# Lan.net
KiCad netlist of a schematic drawn in Altium Designer
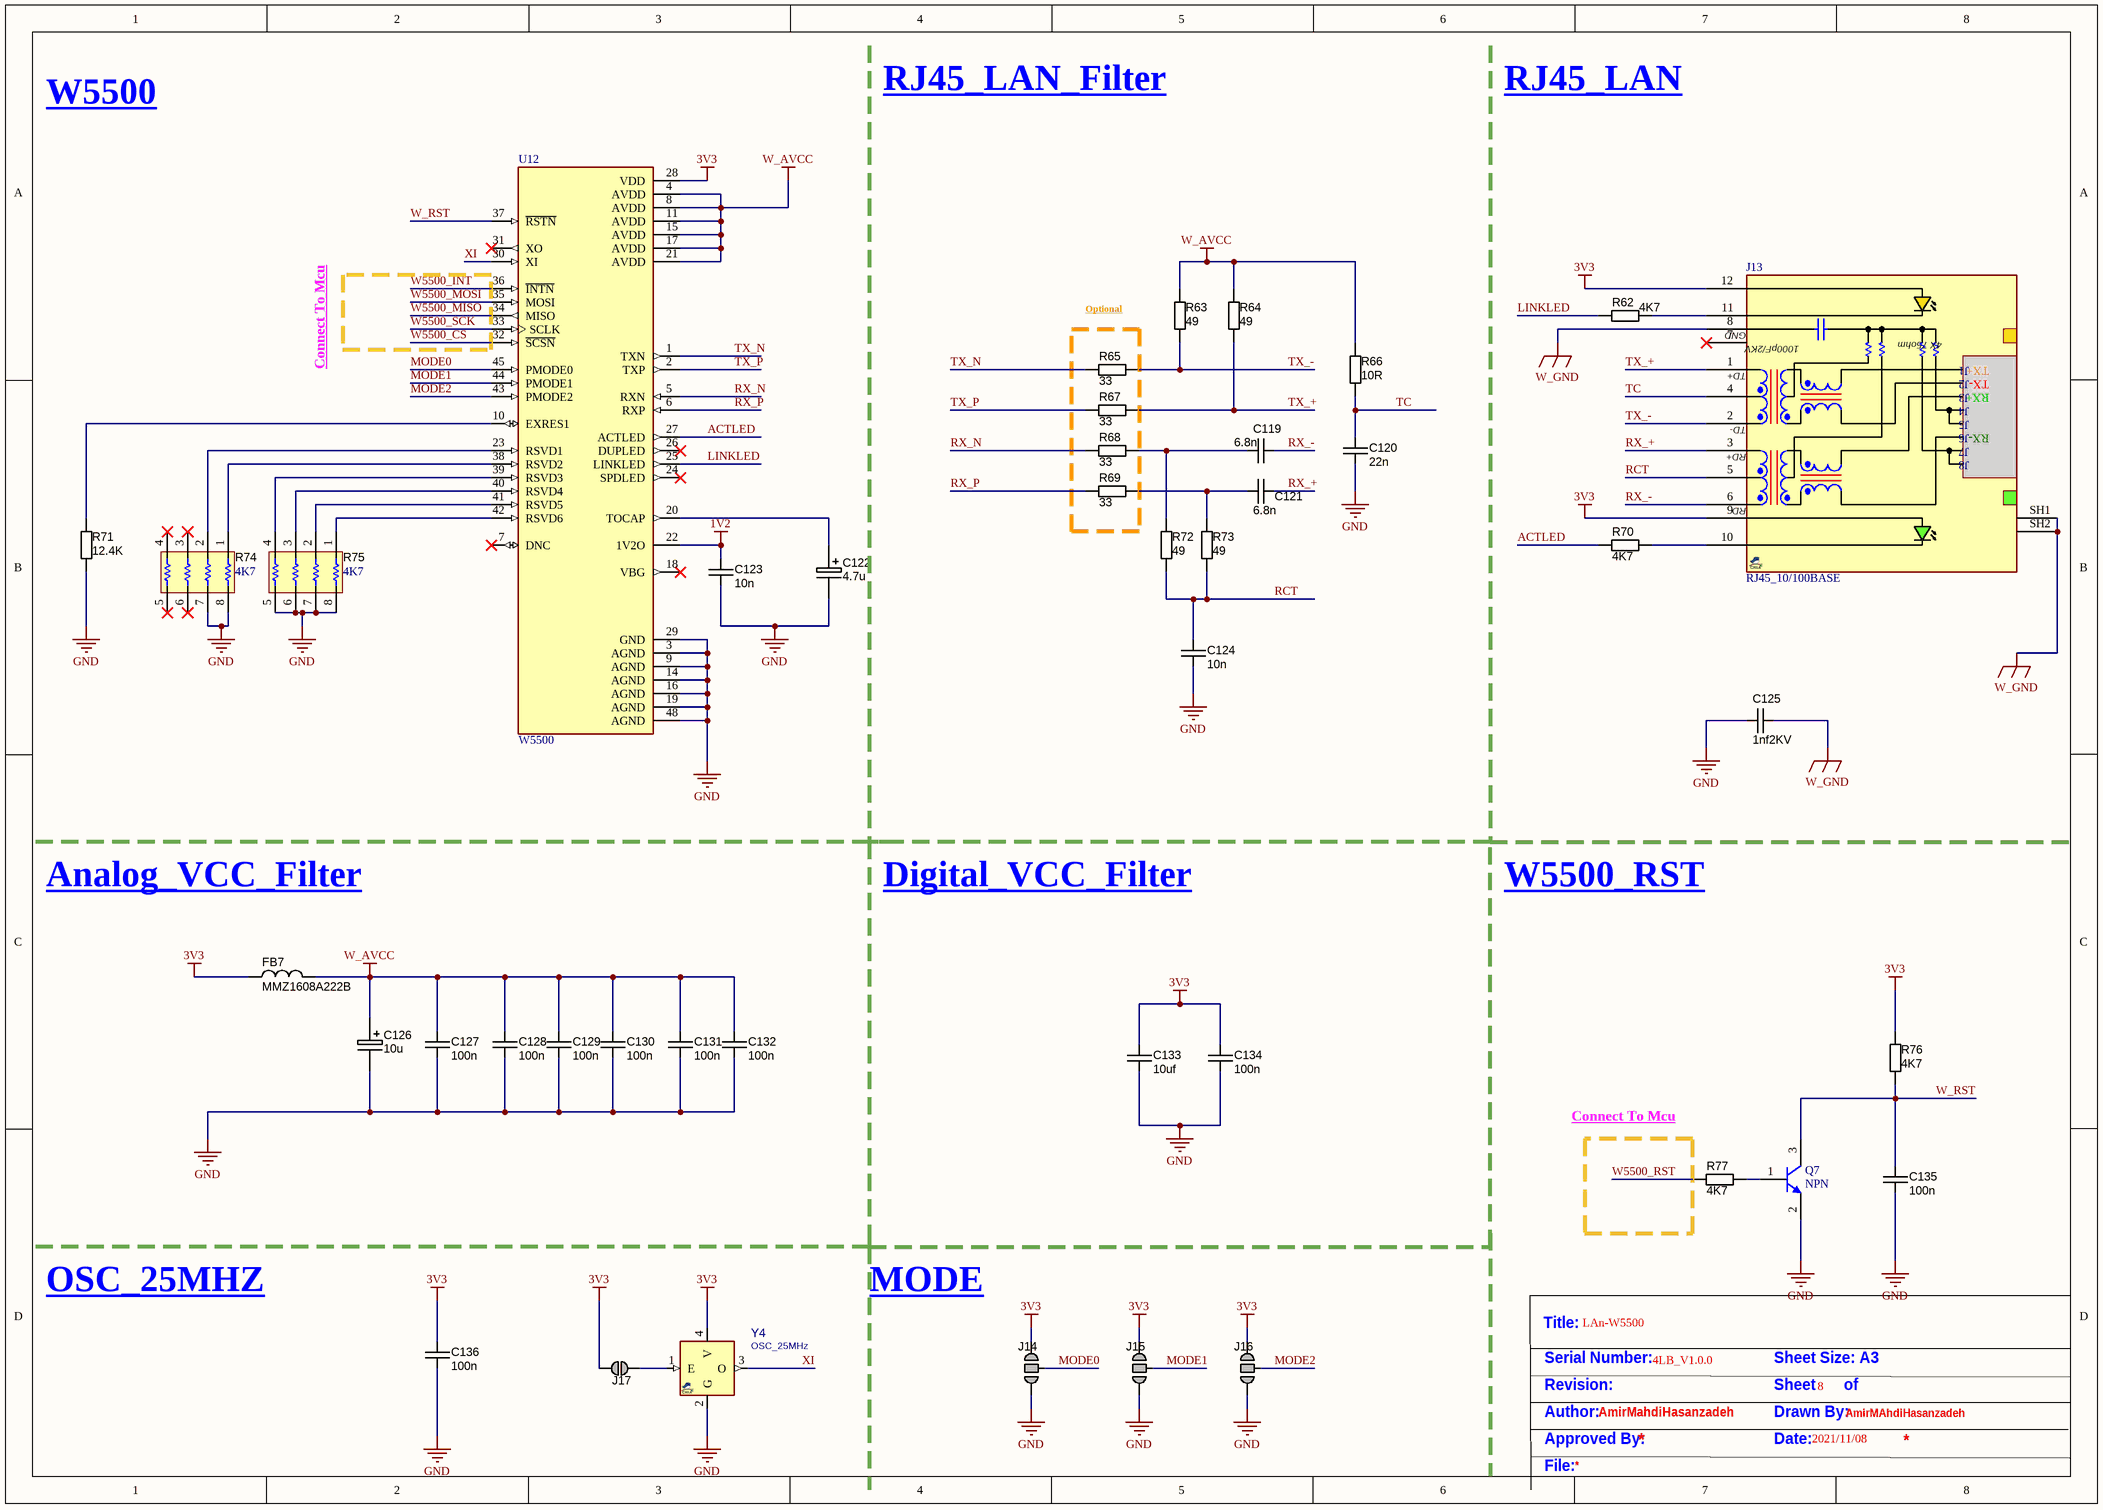
[diagram p0: Lan.SchDoc]

(export (version "E")
  (design (tool "Eeschema 10.0.6"))
  (components
    (comp (ref "C119")
      (value "6.8n")
      (footprint "CAPC1608X90N")
      (description "Capacitor SMD Cer 6.8 10% 50V X7R 0603")
      (fields (field (name "TOLERANCE") "±10%") (field (name "Comment") "approved sub OK"))
      (libsource (lib "PBL - Capacitors") (part "CAPC_100n_0603_X7R_50V_10%"))
    )
    (comp (ref "C120")
      (value "22n")
      (footprint "CAPC1608X90N")
      (description "Capacitor SMD Cer 100nF 10% 50V X7R 0603")
      (fields (field (name "TOLERANCE") "±10%") (field (name "Comment") "approved sub OK"))
      (libsource (lib "PBL - Capacitors") (part "CAPC_100n_0603_X7R_50V_10%"))
    )
    (comp (ref "C121")
      (value "6.8n")
      (footprint "CAPC1608X90N")
      (description "Capacitor SMD Cer 6.8nf 10% 50V X7R 0603")
      (fields (field (name "TOLERANCE") "±10%") (field (name "Comment") "approved sub OK"))
      (libsource (lib "PBL - Capacitors") (part "CAPC_100n_0603_X7R_50V_10%"))
    )
    (comp (ref "C122")
      (value "4.7u")
      (footprint "C_TN_3216")
      (description "Capacitor SMD Tantalum 4.7uF 10% 16V 3216-18")
      (fields (field (name "TOLERANCE") "±10%"))
      (libsource (lib "PBL - Capacitors") (part "CAPT_4u7_3216_16V"))
    )
    (comp (ref "C123")
      (value "10n")
      (footprint "CAPC1608X90N")
      (description "Capacitor SMD Cer 10nF 10% 50V X7R 0603")
      (fields (field (name "TOLERANCE") "±10%") (field (name "Comment") "approved sub OK"))
      (libsource (lib "PBL - Capacitors") (part "CAPC_100n_0603_X7R_50V_10%"))
    )
    (comp (ref "C124")
      (value "10n")
      (footprint "CAPC1608X90N")
      (description "Capacitor SMD Cer 100nF 10% 50V X7R 0603")
      (fields (field (name "TOLERANCE") "±10%") (field (name "Comment") "approved sub OK"))
      (libsource (lib "PBL - Capacitors") (part "CAPC_100n_0603_X7R_50V_10%"))
    )
    (comp (ref "C125")
      (value "1nf2KV")
      (footprint "C1206")
      (description "Capacitor SMD Cer 1nF 10% 2kv X7R 0603")
      (fields (field (name "TOLERANCE") "±10%") (field (name "Comment") "approved sub OK"))
      (libsource (lib "PBL - Capacitors") (part "CAPC_100n_0603_X7R_50V_10%"))
    )
    (comp (ref "C126")
      (value "10u")
      (footprint "C_TN_3216")
      (description "Capacitor SMD Tantalum 10uF 10% 16V 3216-18")
      (fields (field (name "TOLERANCE") "±10%"))
      (libsource (lib "PBL - Capacitors") (part "CAPT_4u7_3216_16V"))
    )
    (comp (ref "C127")
      (value "100n")
      (footprint "CAPC1608X90N")
      (description "Capacitor SMD Cer 100nF 10% 50V X7R 0603")
      (fields (field (name "TOLERANCE") "±10%") (field (name "Comment") "approved sub OK"))
      (libsource (lib "PBL - Capacitors") (part "CAPC_100n_0603_X7R_50V_10%"))
    )
    (comp (ref "C128")
      (value "100n")
      (footprint "CAPC1608X90N")
      (description "Capacitor SMD Cer 100nF 10% 50V X7R 0603")
      (fields (field (name "TOLERANCE") "±10%") (field (name "Comment") "approved sub OK"))
      (libsource (lib "PBL - Capacitors") (part "CAPC_100n_0603_X7R_50V_10%"))
    )
    (comp (ref "C129")
      (value "100n")
      (footprint "CAPC1608X90N")
      (description "Capacitor SMD Cer 100nF 10% 50V X7R 0603")
      (fields (field (name "TOLERANCE") "±10%") (field (name "Comment") "approved sub OK"))
      (libsource (lib "PBL - Capacitors") (part "CAPC_100n_0603_X7R_50V_10%"))
    )
    (comp (ref "C130")
      (value "100n")
      (footprint "CAPC1608X90N")
      (description "Capacitor SMD Cer 100nF 10% 50V X7R 0603")
      (fields (field (name "TOLERANCE") "±10%") (field (name "Comment") "approved sub OK"))
      (libsource (lib "PBL - Capacitors") (part "CAPC_100n_0603_X7R_50V_10%"))
    )
    (comp (ref "C131")
      (value "100n")
      (footprint "CAPC1608X90N")
      (description "Capacitor SMD Cer 100nF 10% 50V X7R 0603")
      (fields (field (name "TOLERANCE") "±10%") (field (name "Comment") "approved sub OK"))
      (libsource (lib "PBL - Capacitors") (part "CAPC_100n_0603_X7R_50V_10%"))
    )
    (comp (ref "C132")
      (value "100n")
      (footprint "CAPC1608X90N")
      (description "Capacitor SMD Cer 100nF 10% 50V X7R 0603")
      (fields (field (name "TOLERANCE") "±10%") (field (name "Comment") "approved sub OK"))
      (libsource (lib "PBL - Capacitors") (part "CAPC_100n_0603_X7R_50V_10%"))
    )
    (comp (ref "C133")
      (value "10uf")
      (footprint "CAPC1608X90N")
      (description "Capacitor SMD Cer 100nF 10% 50V X7R 0603")
      (fields (field (name "TOLERANCE") "±10%") (field (name "Comment") "approved sub OK"))
      (libsource (lib "PBL - Capacitors") (part "CAPC_100n_0603_X7R_50V_10%"))
    )
    (comp (ref "C134")
      (value "100n")
      (footprint "CAPC1608X90N")
      (description "Capacitor SMD Cer 100nF 10% 50V X7R 0603")
      (fields (field (name "TOLERANCE") "±10%") (field (name "Comment") "approved sub OK"))
      (libsource (lib "PBL - Capacitors") (part "CAPC_100n_0603_X7R_50V_10%"))
    )
    (comp (ref "C135")
      (value "100n")
      (footprint "CAPC1608X90N")
      (description "Capacitor SMD Cer 100nF 10% 50V X7R 0603")
      (fields (field (name "TOLERANCE") "±10%") (field (name "Comment") "approved sub OK"))
      (libsource (lib "PBL - Capacitors") (part "CAPC_100n_0603_X7R_50V_10%"))
    )
    (comp (ref "C136")
      (value "100n")
      (footprint "CAPC1608X90N")
      (description "Capacitor SMD Cer 100nF 10% 50V X7R 0603")
      (fields (field (name "TOLERANCE") "±10%") (field (name "Comment") "approved sub OK"))
      (libsource (lib "PBL - Capacitors") (part "CAPC_100n_0603_X7R_50V_10%"))
    )
    (comp (ref "FB7")
      (value "2K2 @ 100 MHz")
      (footprint "FBC1608X95N")
      (description "Ferrite bead 2.2K Ohm at 100 MHz 200mA 0603 SMD")
      (fields (field (name "MANUFACTURER PART NUMBER 1") "MMZ1608A222B"))
      (libsource (lib "PBL - Inductors") (part "FERRITE_2K2-100MHz_0603"))
    )
    (comp (ref "J13")
      (value "RJ45_10/100BASE")
      (footprint "RJ45_8M_HR911105A")
      (description "RJ45, 10/100BASE, G/Y LED")
      (fields (field (name "MANF") "Hanrun") (field (name "MANF_P#") "HR911105A"))
      (libsource (lib "conn_rj_ModularJack") (part "RJ45_HR911105A"))
    )
    (comp (ref "J14")
      (value "Jumper")
      (footprint "Jump_3Way")
      (description "SMD jumper")
      (libsource (lib "PBL - Pads and Jumpers") (part "JUMP_3WAY"))
    )
    (comp (ref "J15")
      (value "Jumper")
      (footprint "Jump_3Way")
      (description "SMD jumper")
      (libsource (lib "PBL - Pads and Jumpers") (part "JUMP_3WAY"))
    )
    (comp (ref "J16")
      (value "Jumper")
      (footprint "Jump_3Way")
      (description "SMD jumper")
      (libsource (lib "PBL - Pads and Jumpers") (part "JUMP_3WAY"))
    )
    (comp (ref "J17")
      (value "Jumper")
      (footprint "JUMP1")
      (description "SMD jumper")
      (libsource (lib "PBL - Pads and Jumpers") (part "JUMP1"))
    )
    (comp (ref "Q7")
      (value "NPN")
      (footprint "SOT23-3")
      (description "NPN Bipolar Transistor")
      (fields (field (name "PUBLISHER") "Altium Limited"))
      (libsource (lib "Miscellaneous Devices") (part "NPN"))
    )
    (comp (ref "R62")
      (value "4K7")
      (footprint "RESC1608X55N")
      (description "Resistor SMD chip 4.7k Ohm 0.1W 5% 0603")
      (fields (field (name "TOLERANCE") "±5%") (field (name "Comment") "Thick Film"))
      (libsource (lib "") (part "RES_4K7_0603_5%_1"))
    )
    (comp (ref "R63")
      (value "49")
      (footprint "RESC1608X55N")
      (description "Resistor SMD chip 49 Ohm 0.1W 5% 0603")
      (fields (field (name "TOLERANCE") "±5%") (field (name "Comment") "Thick Film"))
      (libsource (lib "PBL - Resistors") (part "RES_4K7_0603_5%"))
    )
    (comp (ref "R64")
      (value "49")
      (footprint "RESC1608X55N")
      (description "Resistor SMD chip 49 Ohm 0.1W 5% 0603")
      (fields (field (name "TOLERANCE") "±5%") (field (name "Comment") "Thick Film"))
      (libsource (lib "PBL - Resistors") (part "RES_4K7_0603_5%"))
    )
    (comp (ref "R65")
      (value "33")
      (footprint "RESC1608X55N")
      (description "Resistor SMD chip 33 Ohm 0.1W 5% 0603")
      (fields (field (name "TOLERANCE") "±5%") (field (name "Comment") "Thick Film"))
      (libsource (lib "") (part "RES_4K7_0603_5%_1"))
    )
    (comp (ref "R66")
      (value "10R")
      (footprint "RESC1608X55N")
      (description "Resistor SMD chip 10 Ohm 0.1W 5% 0603")
      (fields (field (name "TOLERANCE") "±5%") (field (name "Comment") "Thick Film"))
      (libsource (lib "PBL - Resistors") (part "RES_4K7_0603_5%"))
    )
    (comp (ref "R67")
      (value "33")
      (footprint "RESC1608X55N")
      (description "Resistor SMD chip 33 Ohm 0.1W 5% 0603")
      (fields (field (name "TOLERANCE") "±5%") (field (name "Comment") "Thick Film"))
      (libsource (lib "") (part "RES_4K7_0603_5%_1"))
    )
    (comp (ref "R68")
      (value "33")
      (footprint "RESC1608X55N")
      (description "Resistor SMD chip 33 Ohm 0.1W 5% 0603")
      (fields (field (name "TOLERANCE") "±5%") (field (name "Comment") "Thick Film"))
      (libsource (lib "") (part "RES_4K7_0603_5%_1"))
    )
    (comp (ref "R69")
      (value "33")
      (footprint "RESC1608X55N")
      (description "Resistor SMD chip 33 Ohm 0.1W 5% 0603")
      (fields (field (name "TOLERANCE") "±5%") (field (name "Comment") "Thick Film"))
      (libsource (lib "") (part "RES_4K7_0603_5%_1"))
    )
    (comp (ref "R70")
      (value "4K7")
      (footprint "RESC1608X55N")
      (description "Resistor SMD chip 4.7k Ohm 0.1W 5% 0603")
      (fields (field (name "TOLERANCE") "±5%") (field (name "Comment") "Thick Film"))
      (libsource (lib "") (part "RES_4K7_0603_5%_1"))
    )
    (comp (ref "R71")
      (value "12.4K")
      (footprint "RESC1608X55N")
      (description "Resistor SMD chip 12.4K Ohm 0.1W 1% 0603")
      (fields (field (name "TOLERANCE") "±5%") (field (name "Comment") "Thick Film"))
      (libsource (lib "") (part "RES_4K7_0603_5%_1"))
    )
    (comp (ref "R72")
      (value "49")
      (footprint "RESC1608X55N")
      (description "Resistor SMD chip 49 Ohm 0.1W 5% 0603")
      (fields (field (name "TOLERANCE") "±5%") (field (name "Comment") "Thick Film"))
      (libsource (lib "PBL - Resistors") (part "RES_4K7_0603_5%"))
    )
    (comp (ref "R73")
      (value "49")
      (footprint "RESC1608X55N")
      (description "Resistor SMD chip 49 Ohm 0.1W 5% 0603")
      (fields (field (name "TOLERANCE") "±5%") (field (name "Comment") "Thick Film"))
      (libsource (lib "PBL - Resistors") (part "RES_4K7_0603_5%"))
    )
    (comp (ref "R74")
      (value "4K7")
      (footprint "RP0603X4")
      (description "Resistor Array SMD")
      (libsource (lib "Resistor") (part "Resistor Array SMD"))
    )
    (comp (ref "R75")
      (value "4K7")
      (footprint "RP0603X4")
      (description "Resistor Array SMD")
      (libsource (lib "Resistor") (part "Resistor Array SMD"))
    )
    (comp (ref "R76")
      (value "4K7")
      (footprint "RESC1608X55N")
      (description "Resistor SMD chip 4.7k Ohm 0.1W 5% 0603")
      (fields (field (name "TOLERANCE") "±5%") (field (name "Comment") "Thick Film"))
      (libsource (lib "") (part "RES_4K7_0603_5%_2"))
    )
    (comp (ref "R77")
      (value "4K7")
      (footprint "RESC1608X55N")
      (description "Resistor SMD chip 4.7k Ohm 0.1W 5% 0603")
      (fields (field (name "TOLERANCE") "±5%") (field (name "Comment") "Thick Film"))
      (libsource (lib "PBL - Resistors") (part "RES_4K7_0603_5%"))
    )
    (comp (ref "U12")
      (value "W5500")
      (footprint "LQFP-48_N")
      (description "Socket Contact Silver 17-20 AWG Crimp Power")
      (fields (field (name "MF") "WIZnet"))
      (libsource (lib "W5500") (part "W5500"))
    )
    (comp (ref "Y4")
      (value "OSC_25MHz")
      (footprint "XTL_4_2520")
      (description "CLOCK OSCILLATOR, 25MHz, 10PPM, 3.2X2.5mm")
      (fields (field (name "MANF") "ECS") (field (name "MANF_P#") "ECS-3225S18-250-FN-TR"))
      (libsource (lib "crystal_osc") (part "OSC_4_25MHz_3225E"))
    )
  )
  (nets
    (net (code "1") (name "/ACTLED") (class "Default")
      (node (ref "R70") (pin "1") (pinfunction "1_1") (pintype "passive"))
      (node (ref "U12") (pin "27") (pinfunction "ACTLED_27") (pintype "output"))
    )
    (net (code "2") (name "/LINKLED") (class "Default")
      (node (ref "R62") (pin "1") (pinfunction "1_1") (pintype "passive"))
      (node (ref "U12") (pin "25") (pinfunction "LINKLED_25") (pintype "output"))
    )
    (net (code "3") (name "/MODE0") (class "Default")
      (node (ref "J14") (pin "2") (pinfunction "2_2") (pintype "passive"))
      (node (ref "U12") (pin "45") (pinfunction "PMODE0_45") (pintype "input"))
    )
    (net (code "4") (name "/MODE1") (class "Default")
      (node (ref "J15") (pin "2") (pinfunction "2_2") (pintype "passive"))
      (node (ref "U12") (pin "44") (pinfunction "PMODE1_44") (pintype "input"))
    )
    (net (code "5") (name "/MODE2") (class "Default")
      (node (ref "J16") (pin "2") (pinfunction "2_2") (pintype "passive"))
      (node (ref "U12") (pin "43") (pinfunction "PMODE2_43") (pintype "input"))
    )
    (net (code "6") (name "/RCT") (class "Default")
      (node (ref "C124") (pin "1") (pintype "passive"))
      (node (ref "J13") (pin "5") (pinfunction "RCT_5") (pintype "passive"))
      (node (ref "R72") (pin "1") (pinfunction "1_1") (pintype "passive"))
      (node (ref "R73") (pin "1") (pinfunction "1_1") (pintype "passive"))
    )
    (net (code "7") (name "/RX_+") (class "Default")
      (node (ref "C121") (pin "2") (pintype "passive"))
      (node (ref "J13") (pin "3") (pinfunction "RD+_3") (pintype "passive"))
    )
    (net (code "8") (name "/RX_-") (class "Default")
      (node (ref "C119") (pin "2") (pintype "passive"))
      (node (ref "J13") (pin "6") (pinfunction "RD-_6") (pintype "passive"))
    )
    (net (code "9") (name "/RX_N") (class "Default")
      (node (ref "R68") (pin "1") (pinfunction "1_1") (pintype "passive"))
      (node (ref "U12") (pin "5") (pinfunction "RXN_5") (pintype "input"))
    )
    (net (code "10") (name "/RX_P") (class "Default")
      (node (ref "R69") (pin "1") (pinfunction "1_1") (pintype "passive"))
      (node (ref "U12") (pin "6") (pinfunction "RXP_6") (pintype "input"))
    )
    (net (code "11") (name "/TC") (class "Default")
      (node (ref "C120") (pin "1") (pintype "passive"))
      (node (ref "J13") (pin "4") (pinfunction "TCT_4") (pintype "passive"))
      (node (ref "R66") (pin "1") (pinfunction "1_1") (pintype "passive"))
    )
    (net (code "12") (name "/TX_+") (class "Default")
      (node (ref "J13") (pin "1") (pinfunction "TD+_1") (pintype "passive"))
      (node (ref "R64") (pin "1") (pinfunction "1_1") (pintype "passive"))
      (node (ref "R67") (pin "2") (pinfunction "2_2") (pintype "passive"))
    )
    (net (code "13") (name "/TX_-") (class "Default")
      (node (ref "J13") (pin "2") (pinfunction "TD-_2") (pintype "passive"))
      (node (ref "R63") (pin "1") (pinfunction "1_1") (pintype "passive"))
      (node (ref "R65") (pin "2") (pinfunction "2_2") (pintype "passive"))
    )
    (net (code "14") (name "/TX_N") (class "Default")
      (node (ref "R65") (pin "1") (pinfunction "1_1") (pintype "passive"))
      (node (ref "U12") (pin "1") (pinfunction "TXN_1") (pintype "output"))
    )
    (net (code "15") (name "/TX_P") (class "Default")
      (node (ref "R67") (pin "1") (pinfunction "1_1") (pintype "passive"))
      (node (ref "U12") (pin "2") (pinfunction "TXP_2") (pintype "output"))
    )
    (net (code "16") (name "/W5500_CS") (class "Default")
      (node (ref "U12") (pin "32") (pinfunction "~{SCSN}_32") (pintype "input"))
    )
    (net (code "17") (name "/W5500_INT") (class "Default")
      (node (ref "U12") (pin "36") (pinfunction "~{INTN}_36") (pintype "input"))
    )
    (net (code "18") (name "/W5500_MISO") (class "Default")
      (node (ref "U12") (pin "34") (pinfunction "MISO_34") (pintype "output"))
    )
    (net (code "19") (name "/W5500_MOSI") (class "Default")
      (node (ref "U12") (pin "35") (pinfunction "MOSI_35") (pintype "input"))
    )
    (net (code "20") (name "/W5500_RST") (class "Default")
      (node (ref "R77") (pin "1") (pinfunction "1_1") (pintype "passive"))
    )
    (net (code "21") (name "/W5500_SCK") (class "Default")
      (node (ref "U12") (pin "33") (pinfunction "SCLK_33") (pintype "input"))
    )
    (net (code "22") (name "/W_RST") (class "Default")
      (node (ref "C135") (pin "1") (pintype "passive"))
      (node (ref "Q7") (pin "3") (pinfunction "C_3") (pintype "passive"))
      (node (ref "R76") (pin "2") (pinfunction "2_2") (pintype "passive"))
      (node (ref "U12") (pin "37") (pinfunction "~{RSTN}_37") (pintype "input"))
    )
    (net (code "23") (name "/XI") (class "Default")
      (node (ref "U12") (pin "30") (pinfunction "XI_30") (pintype "input"))
      (node (ref "Y4") (pin "3") (pinfunction "O_3") (pintype "output"))
    )
    (net (code "24") (name "1V2") (class "Default")
      (node (ref "C123") (pin "1") (pintype "passive"))
      (node (ref "U12") (pin "22") (pinfunction "1V2O_22") (pintype "power_in"))
    )
    (net (code "25") (name "3V3") (class "Default")
      (node (ref "C133") (pin "1") (pintype "passive"))
      (node (ref "C134") (pin "1") (pintype "passive"))
      (node (ref "C136") (pin "1") (pintype "passive"))
      (node (ref "FB7") (pin "1") (pinfunction "1_1") (pintype "passive"))
      (node (ref "J13") (pin "12") (pinfunction "YLED+_12") (pintype "passive"))
      (node (ref "J13") (pin "9") (pinfunction "GLED+_9") (pintype "passive"))
      (node (ref "J14") (pin "3") (pinfunction "3_3") (pintype "passive"))
      (node (ref "J15") (pin "3") (pinfunction "3_3") (pintype "passive"))
      (node (ref "J16") (pin "3") (pinfunction "3_3") (pintype "passive"))
      (node (ref "J17") (pin "2") (pintype "passive"))
      (node (ref "R76") (pin "1") (pinfunction "1_1") (pintype "passive"))
      (node (ref "U12") (pin "28") (pinfunction "VDD_28") (pintype "power_in"))
      (node (ref "Y4") (pin "4") (pinfunction "V_4") (pintype "power_in"))
    )
    (net (code "26") (name "GND") (class "Default")
      (node (ref "C120") (pin "2") (pintype "passive"))
      (node (ref "C122") (pin "2") (pintype "passive"))
      (node (ref "C123") (pin "2") (pintype "passive"))
      (node (ref "C124") (pin "2") (pintype "passive"))
      (node (ref "C125") (pin "1") (pintype "passive"))
      (node (ref "C126") (pin "2") (pintype "passive"))
      (node (ref "C127") (pin "2") (pintype "passive"))
      (node (ref "C128") (pin "2") (pintype "passive"))
      (node (ref "C129") (pin "2") (pintype "passive"))
      (node (ref "C130") (pin "2") (pintype "passive"))
      (node (ref "C131") (pin "2") (pintype "passive"))
      (node (ref "C132") (pin "2") (pintype "passive"))
      (node (ref "C133") (pin "2") (pintype "passive"))
      (node (ref "C134") (pin "2") (pintype "passive"))
      (node (ref "C135") (pin "2") (pintype "passive"))
      (node (ref "C136") (pin "2") (pintype "passive"))
      (node (ref "J14") (pin "1") (pinfunction "1_1") (pintype "passive"))
      (node (ref "J15") (pin "1") (pinfunction "1_1") (pintype "passive"))
      (node (ref "J16") (pin "1") (pinfunction "1_1") (pintype "passive"))
      (node (ref "Q7") (pin "2") (pinfunction "E_2") (pintype "passive"))
      (node (ref "R71") (pin "1") (pinfunction "1_1") (pintype "passive"))
      (node (ref "R74") (pin "7") (pinfunction "7_7") (pintype "passive"))
      (node (ref "R74") (pin "8") (pinfunction "8_8") (pintype "passive"))
      (node (ref "R75") (pin "5") (pinfunction "5_5") (pintype "passive"))
      (node (ref "R75") (pin "6") (pinfunction "6_6") (pintype "passive"))
      (node (ref "R75") (pin "7") (pinfunction "7_7") (pintype "passive"))
      (node (ref "R75") (pin "8") (pinfunction "8_8") (pintype "passive"))
      (node (ref "U12") (pin "14") (pinfunction "AGND_14") (pintype "power_in"))
      (node (ref "U12") (pin "16") (pinfunction "AGND_16") (pintype "power_in"))
      (node (ref "U12") (pin "19") (pinfunction "AGND_19") (pintype "power_in"))
      (node (ref "U12") (pin "29") (pinfunction "GND_29") (pintype "passive"))
      (node (ref "U12") (pin "3") (pinfunction "AGND_3") (pintype "power_in"))
      (node (ref "U12") (pin "48") (pinfunction "AGND_48") (pintype "power_in"))
      (node (ref "U12") (pin "9") (pinfunction "AGND_9") (pintype "power_in"))
      (node (ref "Y4") (pin "2") (pinfunction "G_2") (pintype "power_in"))
    )
    (net (code "27") (name "Net-(C119-Pad1)") (class "Default")
      (node (ref "C119") (pin "1") (pintype "passive"))
      (node (ref "R68") (pin "2") (pinfunction "2_2") (pintype "passive"))
      (node (ref "R72") (pin "2") (pinfunction "2_2") (pintype "passive"))
    )
    (net (code "28") (name "Net-(C121-Pad1)") (class "Default")
      (node (ref "C121") (pin "1") (pintype "passive"))
      (node (ref "R69") (pin "2") (pinfunction "2_2") (pintype "passive"))
      (node (ref "R73") (pin "2") (pinfunction "2_2") (pintype "passive"))
    )
    (net (code "29") (name "Net-(J13-GLED-)") (class "Default")
      (node (ref "J13") (pin "10") (pinfunction "GLED-_10") (pintype "passive"))
      (node (ref "R70") (pin "2") (pinfunction "2_2") (pintype "passive"))
    )
    (net (code "30") (name "Net-(J13-YLED-)") (class "Default")
      (node (ref "J13") (pin "11") (pinfunction "YLED-_11") (pintype "passive"))
      (node (ref "R62") (pin "2") (pinfunction "2_2") (pintype "passive"))
    )
    (net (code "31") (name "Net-(Q7-B)") (class "Default")
      (node (ref "Q7") (pin "1") (pinfunction "B_1") (pintype "passive"))
      (node (ref "R77") (pin "2") (pinfunction "2_2") (pintype "passive"))
    )
    (net (code "32") (name "Net-(U12-EXRES1)") (class "Default")
      (node (ref "R71") (pin "2") (pinfunction "2_2") (pintype "passive"))
      (node (ref "U12") (pin "10") (pinfunction "EXRES1_10") (pintype "bidirectional"))
    )
    (net (code "33") (name "Net-(U12-RSVD1)") (class "Default")
      (node (ref "R74") (pin "2") (pinfunction "2_2") (pintype "passive"))
      (node (ref "U12") (pin "23") (pinfunction "RSVD1_23") (pintype "input"))
    )
    (net (code "34") (name "Net-(U12-RSVD2)") (class "Default")
      (node (ref "R74") (pin "1") (pinfunction "1_1") (pintype "passive"))
      (node (ref "U12") (pin "38") (pinfunction "RSVD2_38") (pintype "input"))
    )
    (net (code "35") (name "Net-(U12-RSVD3)") (class "Default")
      (node (ref "R75") (pin "4") (pinfunction "4_4") (pintype "passive"))
      (node (ref "U12") (pin "39") (pinfunction "RSVD3_39") (pintype "input"))
    )
    (net (code "36") (name "Net-(U12-RSVD4)") (class "Default")
      (node (ref "R75") (pin "3") (pinfunction "3_3") (pintype "passive"))
      (node (ref "U12") (pin "40") (pinfunction "RSVD4_40") (pintype "input"))
    )
    (net (code "37") (name "Net-(U12-RSVD5)") (class "Default")
      (node (ref "R75") (pin "2") (pinfunction "2_2") (pintype "passive"))
      (node (ref "U12") (pin "41") (pinfunction "RSVD5_41") (pintype "input"))
    )
    (net (code "38") (name "Net-(U12-RSVD6)") (class "Default")
      (node (ref "R75") (pin "1") (pinfunction "1_1") (pintype "passive"))
      (node (ref "U12") (pin "42") (pinfunction "RSVD6_42") (pintype "input"))
    )
    (net (code "39") (name "Net-(U12-TOCAP)") (class "Default")
      (node (ref "C122") (pin "1") (pintype "passive"))
      (node (ref "U12") (pin "20") (pinfunction "TOCAP_20") (pintype "output"))
    )
    (net (code "40") (name "Net-(Y4-E)") (class "Default")
      (node (ref "J17") (pin "1") (pintype "passive"))
      (node (ref "Y4") (pin "1") (pinfunction "E_1") (pintype "input"))
    )
    (net (code "41") (name "W_AVCC") (class "Default")
      (node (ref "C126") (pin "1") (pintype "passive"))
      (node (ref "C127") (pin "1") (pintype "passive"))
      (node (ref "C128") (pin "1") (pintype "passive"))
      (node (ref "C129") (pin "1") (pintype "passive"))
      (node (ref "C130") (pin "1") (pintype "passive"))
      (node (ref "C131") (pin "1") (pintype "passive"))
      (node (ref "C132") (pin "1") (pintype "passive"))
      (node (ref "FB7") (pin "2") (pinfunction "2_2") (pintype "passive"))
      (node (ref "R63") (pin "2") (pinfunction "2_2") (pintype "passive"))
      (node (ref "R64") (pin "2") (pinfunction "2_2") (pintype "passive"))
      (node (ref "R66") (pin "2") (pinfunction "2_2") (pintype "passive"))
      (node (ref "U12") (pin "11") (pinfunction "AVDD_11") (pintype "power_in"))
      (node (ref "U12") (pin "15") (pinfunction "AVDD_15") (pintype "power_in"))
      (node (ref "U12") (pin "17") (pinfunction "AVDD_17") (pintype "power_in"))
      (node (ref "U12") (pin "21") (pinfunction "AVDD_21") (pintype "power_in"))
      (node (ref "U12") (pin "4") (pinfunction "AVDD_4") (pintype "power_in"))
      (node (ref "U12") (pin "8") (pinfunction "AVDD_8") (pintype "power_in"))
    )
    (net (code "42") (name "W_GND") (class "Default")
      (node (ref "C125") (pin "2") (pintype "passive"))
      (node (ref "J13") (pin "8") (pinfunction "CHSGND_8") (pintype "passive"))
      (node (ref "J13") (pin "SH1") (pinfunction "SH1_SH1") (pintype "passive"))
      (node (ref "J13") (pin "SH2") (pinfunction "SH2_SH2") (pintype "passive"))
    )
    (net (code "43") (name "unconnected-(J13-NC-Pad7)") (class "Default")
      (node (ref "J13") (pin "7") (pinfunction "NC_7") (pintype "passive+no_connect"))
    )
    (net (code "44") (name "unconnected-(R74-Pad3)") (class "Default")
      (node (ref "R74") (pin "3") (pinfunction "3_3") (pintype "passive+no_connect"))
    )
    (net (code "45") (name "unconnected-(R74-Pad4)") (class "Default")
      (node (ref "R74") (pin "4") (pinfunction "4_4") (pintype "passive+no_connect"))
    )
    (net (code "46") (name "unconnected-(R74-Pad5)") (class "Default")
      (node (ref "R74") (pin "5") (pinfunction "5_5") (pintype "passive+no_connect"))
    )
    (net (code "47") (name "unconnected-(R74-Pad6)") (class "Default")
      (node (ref "R74") (pin "6") (pinfunction "6_6") (pintype "passive+no_connect"))
    )
    (net (code "48") (name "unconnected-(U12-DNC-Pad7)") (class "Default")
      (node (ref "U12") (pin "7") (pinfunction "DNC_7") (pintype "bidirectional+no_connect"))
    )
    (net (code "49") (name "unconnected-(U12-DUPLED-Pad26)") (class "Default")
      (node (ref "U12") (pin "26") (pinfunction "DUPLED_26") (pintype "output+no_connect"))
    )
    (net (code "50") (name "unconnected-(U12-SPDLED-Pad24)") (class "Default")
      (node (ref "U12") (pin "24") (pinfunction "SPDLED_24") (pintype "output+no_connect"))
    )
    (net (code "51") (name "unconnected-(U12-VBG-Pad18)") (class "Default")
      (node (ref "U12") (pin "18") (pinfunction "VBG_18") (pintype "output+no_connect"))
    )
    (net (code "52") (name "unconnected-(U12-XO-Pad31)") (class "Default")
      (node (ref "U12") (pin "31") (pinfunction "XO_31") (pintype "output+no_connect"))
    )
  )
)
